# MainBoard.net
KiCad netlist of a schematic drawn in Altium Designer
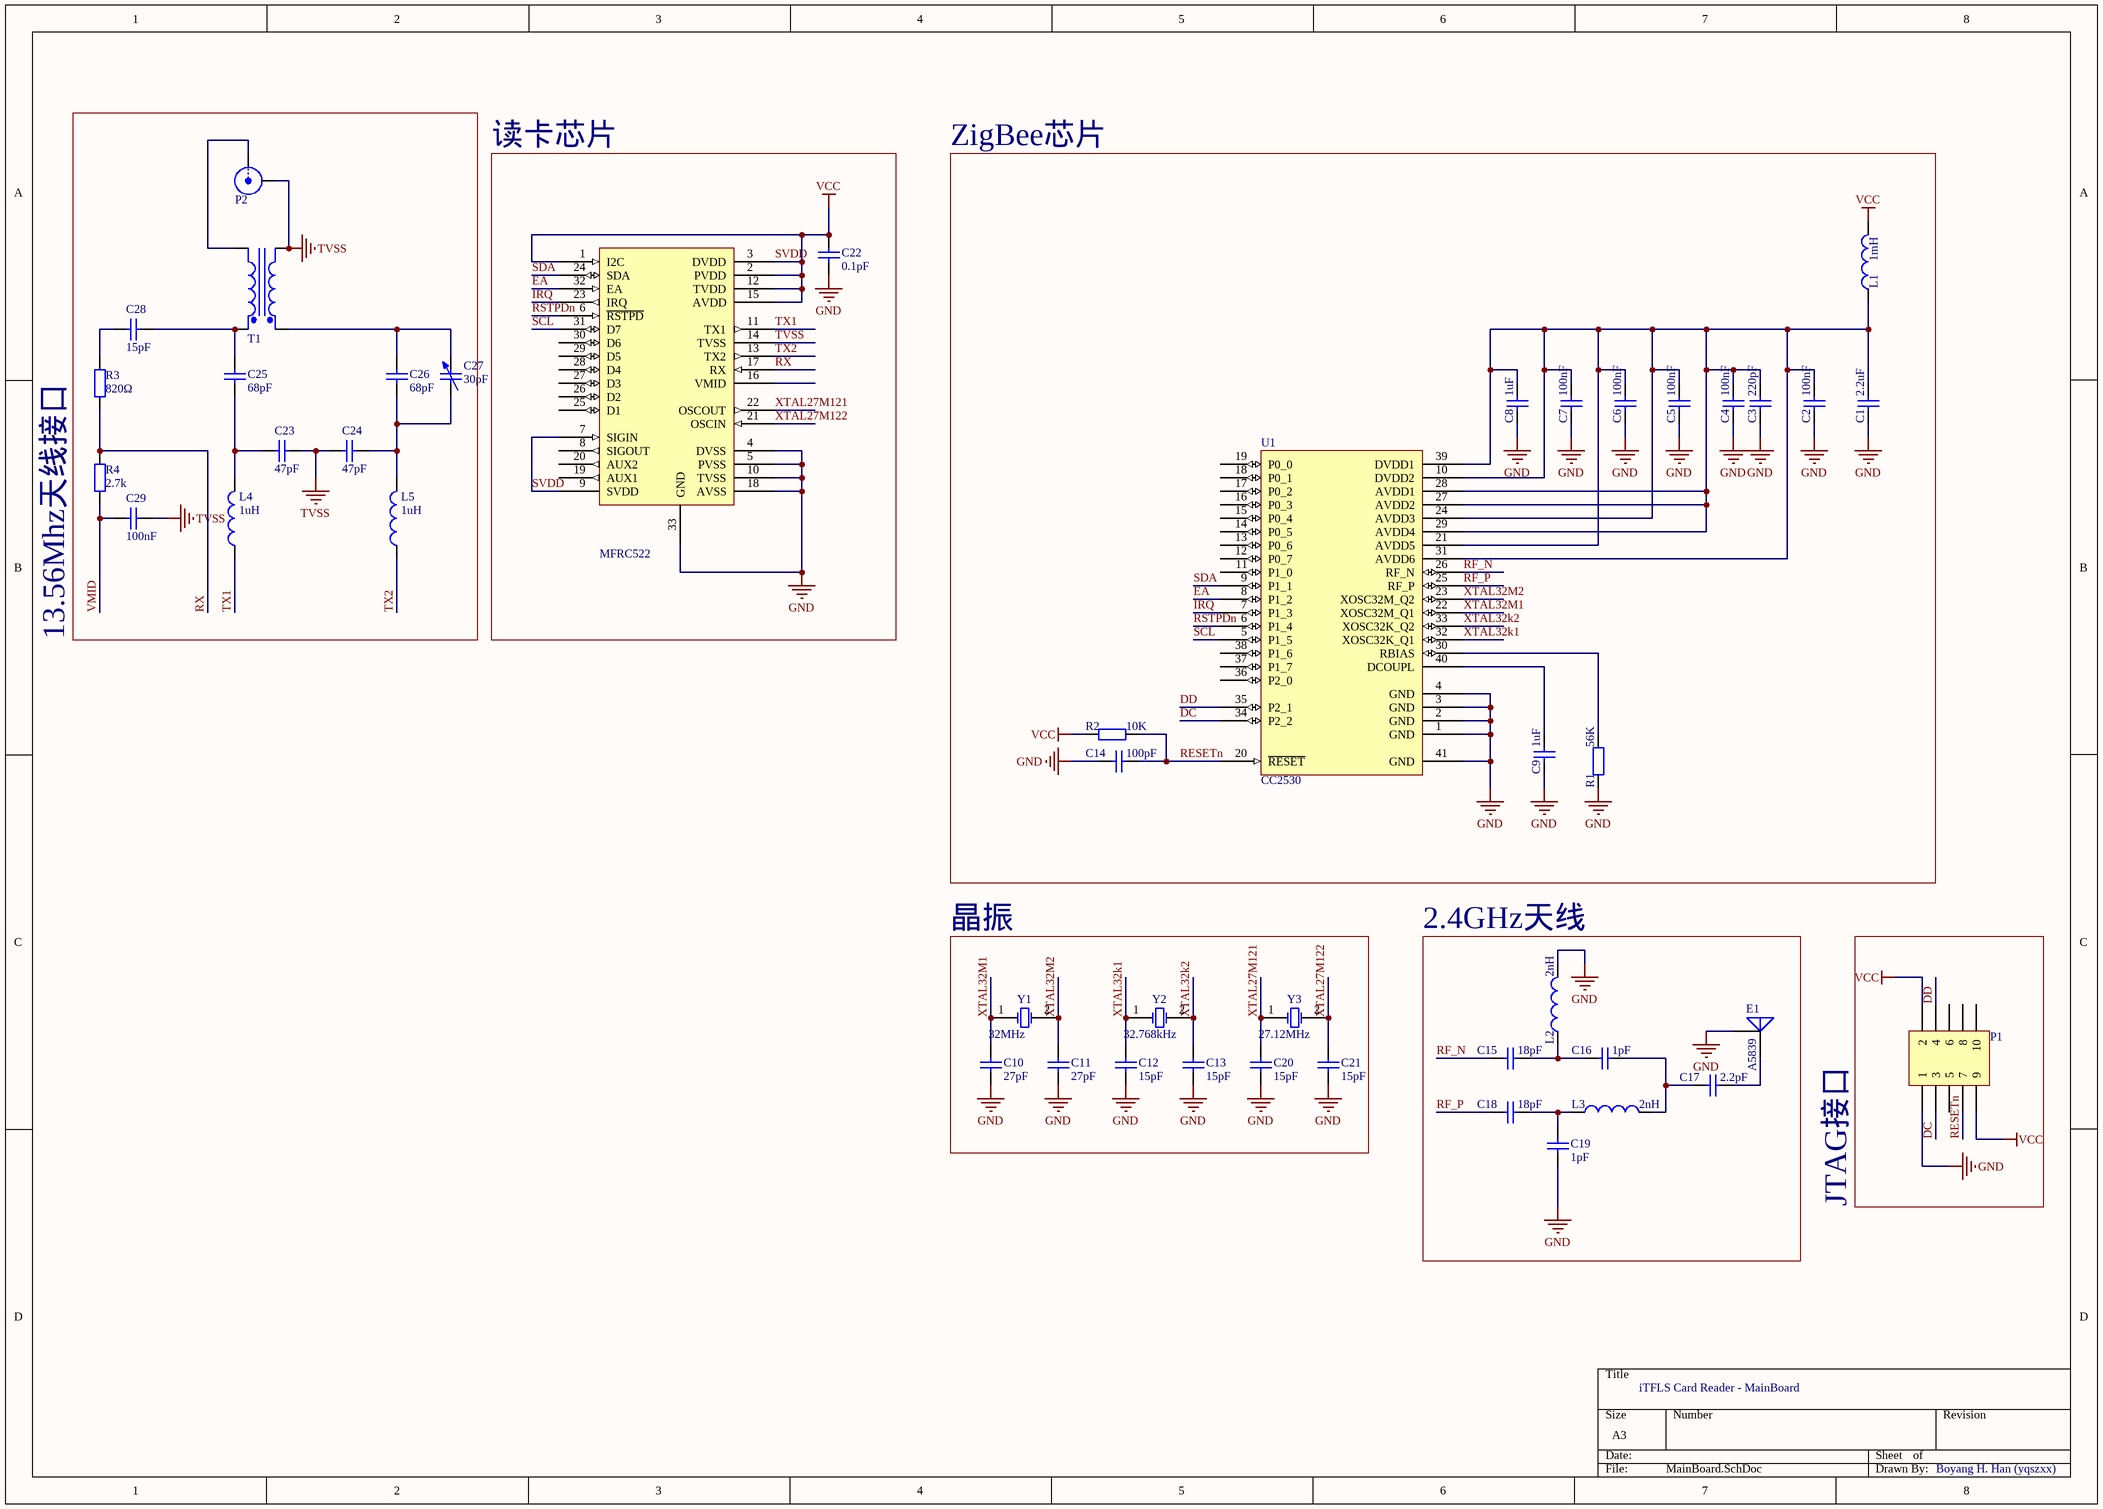
[diagram p0: MainBoard.SchDoc]

(export (version "E")
  (design (tool "Eeschema 10.0.6"))
  (components
    (comp (ref "C1")
      (value "2.2uF")
      (footprint "0603")
      (description "Capacitor")
      (fields (field (name "Comment") "Cap") (field (name "PUBLISHER") "Altium Limited"))
      (libsource (lib "Miscellaneous Devices") (part "Cap"))
    )
    (comp (ref "C2")
      (value "100nF")
      (footprint "0603")
      (description "Capacitor")
      (fields (field (name "Comment") "Cap") (field (name "PUBLISHER") "Altium Limited"))
      (libsource (lib "Miscellaneous Devices") (part "Cap"))
    )
    (comp (ref "C3")
      (value "220pF")
      (footprint "0603")
      (description "Capacitor")
      (fields (field (name "Comment") "Cap") (field (name "PUBLISHER") "Altium Limited"))
      (libsource (lib "Miscellaneous Devices") (part "Cap"))
    )
    (comp (ref "C4")
      (value "100nF")
      (footprint "0603")
      (description "Capacitor")
      (fields (field (name "Comment") "Cap") (field (name "PUBLISHER") "Altium Limited"))
      (libsource (lib "Miscellaneous Devices") (part "Cap"))
    )
    (comp (ref "C5")
      (value "100nF")
      (footprint "0603")
      (description "Capacitor")
      (fields (field (name "Comment") "Cap") (field (name "PUBLISHER") "Altium Limited"))
      (libsource (lib "Miscellaneous Devices") (part "Cap"))
    )
    (comp (ref "C6")
      (value "100nF")
      (footprint "0603")
      (description "Capacitor")
      (fields (field (name "Comment") "Cap") (field (name "PUBLISHER") "Altium Limited"))
      (libsource (lib "Miscellaneous Devices") (part "Cap"))
    )
    (comp (ref "C7")
      (value "100nF")
      (footprint "0603")
      (description "Capacitor")
      (fields (field (name "Comment") "Cap") (field (name "PUBLISHER") "Altium Limited"))
      (libsource (lib "Miscellaneous Devices") (part "Cap"))
    )
    (comp (ref "C8")
      (value "1uF")
      (footprint "0603")
      (description "Capacitor")
      (fields (field (name "Comment") "Cap") (field (name "PUBLISHER") "Altium Limited"))
      (libsource (lib "Miscellaneous Devices") (part "Cap"))
    )
    (comp (ref "C9")
      (value "1uF")
      (footprint "0603")
      (description "Capacitor")
      (fields (field (name "Comment") "Cap") (field (name "PUBLISHER") "Altium Limited"))
      (libsource (lib "Miscellaneous Devices") (part "Cap"))
    )
    (comp (ref "C10")
      (value "27pF")
      (footprint "0603")
      (description "Capacitor")
      (fields (field (name "Comment") "Cap") (field (name "PUBLISHER") "Altium Limited"))
      (libsource (lib "Miscellaneous Devices") (part "Cap"))
    )
    (comp (ref "C11")
      (value "27pF")
      (footprint "0603")
      (description "Capacitor")
      (fields (field (name "Comment") "Cap") (field (name "PUBLISHER") "Altium Limited"))
      (libsource (lib "Miscellaneous Devices") (part "Cap"))
    )
    (comp (ref "C12")
      (value "15pF")
      (footprint "0603")
      (description "Capacitor")
      (fields (field (name "Comment") "Cap") (field (name "PUBLISHER") "Altium Limited"))
      (libsource (lib "Miscellaneous Devices") (part "Cap"))
    )
    (comp (ref "C13")
      (value "15pF")
      (footprint "0603")
      (description "Capacitor")
      (fields (field (name "Comment") "Cap") (field (name "PUBLISHER") "Altium Limited"))
      (libsource (lib "Miscellaneous Devices") (part "Cap"))
    )
    (comp (ref "C14")
      (value "100pF")
      (footprint "0603")
      (description "Capacitor")
      (fields (field (name "Comment") "Cap") (field (name "PUBLISHER") "Altium Limited"))
      (libsource (lib "Miscellaneous Devices") (part "Cap"))
    )
    (comp (ref "C15")
      (value "18pF")
      (footprint "0603")
      (description "Capacitor")
      (fields (field (name "Comment") "Cap") (field (name "PUBLISHER") "Altium Limited"))
      (libsource (lib "Miscellaneous Devices") (part "Cap"))
    )
    (comp (ref "C16")
      (value "1pF")
      (footprint "0603")
      (description "Capacitor")
      (fields (field (name "Comment") "Cap") (field (name "PUBLISHER") "Altium Limited"))
      (libsource (lib "Miscellaneous Devices") (part "Cap"))
    )
    (comp (ref "C17")
      (value "2.2pF")
      (footprint "0603")
      (description "Capacitor")
      (fields (field (name "Comment") "Cap") (field (name "PUBLISHER") "Altium Limited"))
      (libsource (lib "Miscellaneous Devices") (part "Cap"))
    )
    (comp (ref "C18")
      (value "18pF")
      (footprint "0603")
      (description "Capacitor")
      (fields (field (name "Comment") "Cap") (field (name "PUBLISHER") "Altium Limited"))
      (libsource (lib "Miscellaneous Devices") (part "Cap"))
    )
    (comp (ref "C19")
      (value "1pF")
      (footprint "0603")
      (description "Capacitor")
      (fields (field (name "Comment") "Cap") (field (name "PUBLISHER") "Altium Limited"))
      (libsource (lib "Miscellaneous Devices") (part "Cap"))
    )
    (comp (ref "C20")
      (value "15pF")
      (footprint "0603")
      (description "Capacitor")
      (fields (field (name "Comment") "Cap") (field (name "PUBLISHER") "Altium Limited"))
      (libsource (lib "Miscellaneous Devices") (part "Cap"))
    )
    (comp (ref "C21")
      (value "15pF")
      (footprint "0603")
      (description "Capacitor")
      (fields (field (name "Comment") "Cap") (field (name "PUBLISHER") "Altium Limited"))
      (libsource (lib "Miscellaneous Devices") (part "Cap"))
    )
    (comp (ref "C22")
      (value "0.1pF")
      (footprint "0603")
      (description "Capacitor")
      (fields (field (name "Comment") "Cap") (field (name "PUBLISHER") "Altium Limited"))
      (libsource (lib "Miscellaneous Devices") (part "Cap"))
    )
    (comp (ref "C23")
      (value "47pF")
      (footprint "0603")
      (description "Capacitor")
      (fields (field (name "Comment") "Cap") (field (name "PUBLISHER") "Altium Limited"))
      (libsource (lib "Miscellaneous Devices") (part "Cap"))
    )
    (comp (ref "C24")
      (value "47pF")
      (footprint "0603")
      (description "Capacitor")
      (fields (field (name "Comment") "Cap") (field (name "PUBLISHER") "Altium Limited"))
      (libsource (lib "Miscellaneous Devices") (part "Cap"))
    )
    (comp (ref "C25")
      (value "68pF")
      (footprint "0603")
      (description "Capacitor")
      (fields (field (name "Comment") "Cap") (field (name "PUBLISHER") "Altium Limited"))
      (libsource (lib "Miscellaneous Devices") (part "Cap"))
    )
    (comp (ref "C26")
      (value "68pF")
      (footprint "0603")
      (description "Capacitor")
      (fields (field (name "Comment") "Cap") (field (name "PUBLISHER") "Altium Limited"))
      (libsource (lib "Miscellaneous Devices") (part "Cap"))
    )
    (comp (ref "C27")
      (value "30pF")
      (footprint "4x4VC")
      (description "Variable or Adjustable Capacitor")
      (fields (field (name "Comment") "Cap Var") (field (name "PUBLISHER") "Altium Limited"))
      (libsource (lib "Miscellaneous Devices") (part "Cap Var"))
    )
    (comp (ref "C28")
      (value "15pF")
      (footprint "0603")
      (description "Capacitor")
      (fields (field (name "Comment") "Cap") (field (name "PUBLISHER") "Altium Limited"))
      (libsource (lib "Miscellaneous Devices") (part "Cap"))
    )
    (comp (ref "C29")
      (value "100nF")
      (footprint "0603")
      (description "Capacitor")
      (fields (field (name "Comment") "Cap") (field (name "PUBLISHER") "Altium Limited"))
      (libsource (lib "Miscellaneous Devices") (part "Cap"))
    )
    (comp (ref "E1") (value "A5839") (footprint "A5839") (libsource (lib "A5839") (part "A5839")))
    (comp (ref "L1")
      (value "1mH")
      (footprint "0603")
      (description "Inductor")
      (fields (field (name "PUBLISHER") "Altium Limited"))
      (libsource (lib "Miscellaneous Devices") (part "Inductor"))
    )
    (comp (ref "L2")
      (value "2nH")
      (footprint "0603")
      (description "Inductor")
      (fields (field (name "PUBLISHER") "Altium Limited"))
      (libsource (lib "Miscellaneous Devices") (part "Inductor"))
    )
    (comp (ref "L3")
      (value "2nH")
      (footprint "0603")
      (description "Inductor")
      (fields (field (name "PUBLISHER") "Altium Limited"))
      (libsource (lib "Miscellaneous Devices") (part "Inductor"))
    )
    (comp (ref "L4")
      (value "1uH")
      (footprint "0603")
      (description "Inductor")
      (fields (field (name "PUBLISHER") "Altium Limited"))
      (libsource (lib "Miscellaneous Devices") (part "Inductor"))
    )
    (comp (ref "L5")
      (value "1uH")
      (footprint "0603")
      (description "Inductor")
      (fields (field (name "PUBLISHER") "Altium Limited"))
      (libsource (lib "Miscellaneous Devices") (part "Inductor"))
    )
    (comp (ref "P1")
      (value "Header 5X2")
      (footprint "HDR2X5")
      (description "Header, 5-Pin, Dual row")
      (fields (field (name "PUBLISHER") "Altium Limited"))
      (libsource (lib "Miscellaneous Connectors") (part "Header 5X2"))
    )
    (comp (ref "P2")
      (value "U.FL")
      (footprint "U.FL")
      (description "SMB Straight Connector")
      (fields (field (name "PUBLISHER") "Altium Limited"))
      (libsource (lib "Miscellaneous Connectors") (part "SMB"))
    )
    (comp (ref "R1")
      (value "56K")
      (footprint "0603")
      (description "Resistor")
      (fields (field (name "Comment") "Res2") (field (name "PUBLISHER") "Altium Limited"))
      (libsource (lib "") (part "Res2_1"))
    )
    (comp (ref "R2")
      (value "10K")
      (footprint "0603")
      (description "Resistor")
      (fields (field (name "Comment") "Res2") (field (name "PUBLISHER") "Altium Limited"))
      (libsource (lib "Miscellaneous Devices") (part "Res2"))
    )
    (comp (ref "R3")
      (value "820Ω")
      (footprint "0603")
      (description "Resistor")
      (fields (field (name "Comment") "Res2") (field (name "PUBLISHER") "Altium Limited"))
      (libsource (lib "") (part "Res2_1"))
    )
    (comp (ref "R4")
      (value "2.7k")
      (footprint "0603")
      (description "Resistor")
      (fields (field (name "Comment") "Res2") (field (name "PUBLISHER") "Altium Limited"))
      (libsource (lib "") (part "Res2_1"))
    )
    (comp (ref "T1")
      (value "1812WBT-3")
      (footprint "1812WBT-3")
      (libsource (lib "Coilcraft 1812WBT-3") (part "1812WBT-3"))
    )
    (comp (ref "U1") (value "CC2530") (footprint "QFN40") (libsource (lib "CC2530") (part "CC2530")))
    (comp (ref "U2") (value "MFRC522") (footprint "QFN32") (libsource (lib "MFRC522") (part "MFRC522")))
    (comp (ref "Y1")
      (value "32MHz")
      (footprint "XTAL3225")
      (description "Crystal Oscillator")
      (fields (field (name "Comment") "XTAL") (field (name "PUBLISHER") "Altium Limited"))
      (libsource (lib "Miscellaneous Devices") (part "XTAL"))
    )
    (comp (ref "Y2")
      (value "32.768kHz")
      (footprint "XTAL3215")
      (description "Crystal Oscillator")
      (fields (field (name "Comment") "XTAL") (field (name "PUBLISHER") "Altium Limited"))
      (libsource (lib "Miscellaneous Devices") (part "XTAL"))
    )
    (comp (ref "Y3")
      (value "27.12MHz")
      (footprint "XTAL3225")
      (description "Crystal Oscillator")
      (fields (field (name "Comment") "XTAL") (field (name "PUBLISHER") "Altium Limited"))
      (libsource (lib "Miscellaneous Devices") (part "XTAL"))
    )
  )
  (nets
    (net (code "1") (name "/DC") (class "Default")
      (node (ref "P1") (pin "3") (pinfunction "3_3") (pintype "passive"))
      (node (ref "U1") (pin "34") (pinfunction "P2_2_34") (pintype "bidirectional"))
    )
    (net (code "2") (name "/DD") (class "Default")
      (node (ref "P1") (pin "4") (pinfunction "4_4") (pintype "passive"))
      (node (ref "U1") (pin "35") (pinfunction "P2_1_35") (pintype "bidirectional"))
    )
    (net (code "3") (name "/EA") (class "Default")
      (node (ref "U1") (pin "8") (pinfunction "P1_2_8") (pintype "bidirectional"))
      (node (ref "U2") (pin "32") (pinfunction "EA_32") (pintype "input"))
    )
    (net (code "4") (name "/IRQ") (class "Default")
      (node (ref "U1") (pin "7") (pinfunction "P1_3_7") (pintype "bidirectional"))
      (node (ref "U2") (pin "23") (pinfunction "IRQ_23") (pintype "output"))
    )
    (net (code "5") (name "/RESETn") (class "Default")
      (node (ref "C14") (pin "2") (pinfunction "2_2") (pintype "passive"))
      (node (ref "P1") (pin "7") (pinfunction "7_7") (pintype "passive"))
      (node (ref "R2") (pin "2") (pinfunction "2_2") (pintype "passive"))
      (node (ref "U1") (pin "20") (pinfunction "~{RESET}_20") (pintype "input"))
    )
    (net (code "6") (name "/RF_N") (class "Default")
      (node (ref "C15") (pin "1") (pinfunction "1_1") (pintype "passive"))
      (node (ref "U1") (pin "26") (pinfunction "RF_N_26") (pintype "bidirectional"))
    )
    (net (code "7") (name "/RF_P") (class "Default")
      (node (ref "C18") (pin "1") (pinfunction "1_1") (pintype "passive"))
      (node (ref "U1") (pin "25") (pinfunction "RF_P_25") (pintype "bidirectional"))
    )
    (net (code "8") (name "/RSTPDn") (class "Default")
      (node (ref "U1") (pin "6") (pinfunction "P1_4_6") (pintype "bidirectional"))
      (node (ref "U2") (pin "6") (pinfunction "~{RSTPD}_6") (pintype "input"))
    )
    (net (code "9") (name "/RX") (class "Default")
      (node (ref "R3") (pin "1") (pinfunction "1_1") (pintype "passive"))
      (node (ref "R4") (pin "2") (pinfunction "2_2") (pintype "passive"))
      (node (ref "U2") (pin "17") (pinfunction "RX_17") (pintype "input"))
    )
    (net (code "10") (name "/SCL") (class "Default")
      (node (ref "U1") (pin "5") (pinfunction "P1_5_5") (pintype "bidirectional"))
      (node (ref "U2") (pin "31") (pinfunction "D7_31") (pintype "bidirectional"))
    )
    (net (code "11") (name "/SDA") (class "Default")
      (node (ref "U1") (pin "9") (pinfunction "P1_1_9") (pintype "bidirectional"))
      (node (ref "U2") (pin "24") (pinfunction "SDA_24") (pintype "bidirectional"))
    )
    (net (code "12") (name "/TX1") (class "Default")
      (node (ref "L4") (pin "1") (pinfunction "1_1") (pintype "passive"))
      (node (ref "U2") (pin "11") (pinfunction "TX1_11") (pintype "output"))
    )
    (net (code "13") (name "/TX2") (class "Default")
      (node (ref "L5") (pin "1") (pinfunction "1_1") (pintype "passive"))
      (node (ref "U2") (pin "13") (pinfunction "TX2_13") (pintype "output"))
    )
    (net (code "14") (name "/VMID") (class "Default")
      (node (ref "C29") (pin "2") (pinfunction "2_2") (pintype "passive"))
      (node (ref "R4") (pin "1") (pinfunction "1_1") (pintype "passive"))
    )
    (net (code "15") (name "/XTAL27M121") (class "Default")
      (node (ref "C20") (pin "2") (pinfunction "2_2") (pintype "passive"))
      (node (ref "U2") (pin "22") (pinfunction "OSCOUT_22") (pintype "output"))
      (node (ref "Y3") (pin "1") (pinfunction "OSC1_1") (pintype "passive"))
    )
    (net (code "16") (name "/XTAL27M122") (class "Default")
      (node (ref "C21") (pin "2") (pinfunction "2_2") (pintype "passive"))
      (node (ref "U2") (pin "21") (pinfunction "OSCIN_21") (pintype "input"))
      (node (ref "Y3") (pin "2") (pinfunction "OSC2_2") (pintype "passive"))
    )
    (net (code "17") (name "/XTAL32M1") (class "Default")
      (node (ref "C10") (pin "2") (pinfunction "2_2") (pintype "passive"))
      (node (ref "U1") (pin "22") (pinfunction "XOSC32M_Q1_22") (pintype "bidirectional"))
      (node (ref "Y1") (pin "1") (pinfunction "OSC1_1") (pintype "passive"))
    )
    (net (code "18") (name "/XTAL32M2") (class "Default")
      (node (ref "C11") (pin "2") (pinfunction "2_2") (pintype "passive"))
      (node (ref "U1") (pin "23") (pinfunction "XOSC32M_Q2_23") (pintype "bidirectional"))
      (node (ref "Y1") (pin "2") (pinfunction "OSC2_2") (pintype "passive"))
    )
    (net (code "19") (name "/XTAL32k1") (class "Default")
      (node (ref "C12") (pin "2") (pinfunction "2_2") (pintype "passive"))
      (node (ref "U1") (pin "32") (pinfunction "XOSC32K_Q1_32") (pintype "bidirectional"))
      (node (ref "Y2") (pin "1") (pinfunction "OSC1_1") (pintype "passive"))
    )
    (net (code "20") (name "/XTAL32k2") (class "Default")
      (node (ref "C13") (pin "2") (pinfunction "2_2") (pintype "passive"))
      (node (ref "U1") (pin "33") (pinfunction "XOSC32K_Q2_33") (pintype "bidirectional"))
      (node (ref "Y2") (pin "2") (pinfunction "OSC2_2") (pintype "passive"))
    )
    (net (code "21") (name "GND") (class "Default")
      (node (ref "C1") (pin "1") (pinfunction "1_1") (pintype "passive"))
      (node (ref "C10") (pin "1") (pinfunction "1_1") (pintype "passive"))
      (node (ref "C11") (pin "1") (pinfunction "1_1") (pintype "passive"))
      (node (ref "C12") (pin "1") (pinfunction "1_1") (pintype "passive"))
      (node (ref "C13") (pin "1") (pinfunction "1_1") (pintype "passive"))
      (node (ref "C14") (pin "1") (pinfunction "1_1") (pintype "passive"))
      (node (ref "C19") (pin "1") (pinfunction "1_1") (pintype "passive"))
      (node (ref "C2") (pin "1") (pinfunction "1_1") (pintype "passive"))
      (node (ref "C20") (pin "1") (pinfunction "1_1") (pintype "passive"))
      (node (ref "C21") (pin "1") (pinfunction "1_1") (pintype "passive"))
      (node (ref "C22") (pin "1") (pinfunction "1_1") (pintype "passive"))
      (node (ref "C3") (pin "1") (pinfunction "1_1") (pintype "passive"))
      (node (ref "C4") (pin "1") (pinfunction "1_1") (pintype "passive"))
      (node (ref "C5") (pin "1") (pinfunction "1_1") (pintype "passive"))
      (node (ref "C6") (pin "1") (pinfunction "1_1") (pintype "passive"))
      (node (ref "C7") (pin "1") (pinfunction "1_1") (pintype "passive"))
      (node (ref "C8") (pin "1") (pinfunction "1_1") (pintype "passive"))
      (node (ref "C9") (pin "1") (pinfunction "1_1") (pintype "passive"))
      (node (ref "E1") (pin "2") (pinfunction "GND_2") (pintype "passive"))
      (node (ref "L2") (pin "2") (pinfunction "2_2") (pintype "passive"))
      (node (ref "P1") (pin "1") (pinfunction "1_1") (pintype "passive"))
      (node (ref "R1") (pin "1") (pinfunction "1_1") (pintype "passive"))
      (node (ref "U1") (pin "1") (pinfunction "GND_1") (pintype "power_in"))
      (node (ref "U1") (pin "2") (pinfunction "GND_2") (pintype "power_in"))
      (node (ref "U1") (pin "3") (pinfunction "GND_3") (pintype "power_in"))
      (node (ref "U1") (pin "4") (pinfunction "GND_4") (pintype "power_in"))
      (node (ref "U1") (pin "41") (pinfunction "GND_41") (pintype "power_in"))
      (node (ref "U2") (pin "10") (pinfunction "TVSS_10") (pintype "power_in"))
      (node (ref "U2") (pin "18") (pinfunction "AVSS_18") (pintype "power_in"))
      (node (ref "U2") (pin "33") (pinfunction "GND_33") (pintype "power_in"))
      (node (ref "U2") (pin "4") (pinfunction "DVSS_4") (pintype "power_in"))
      (node (ref "U2") (pin "5") (pinfunction "PVSS_5") (pintype "power_in"))
    )
    (net (code "22") (name "Net-(C15-Pad2)") (class "Default")
      (node (ref "C15") (pin "2") (pinfunction "2_2") (pintype "passive"))
      (node (ref "C16") (pin "1") (pinfunction "1_1") (pintype "passive"))
      (node (ref "L2") (pin "1") (pinfunction "1_1") (pintype "passive"))
    )
    (net (code "23") (name "Net-(C16-Pad2)") (class "Default")
      (node (ref "C16") (pin "2") (pinfunction "2_2") (pintype "passive"))
      (node (ref "C17") (pin "1") (pinfunction "1_1") (pintype "passive"))
      (node (ref "L3") (pin "2") (pinfunction "2_2") (pintype "passive"))
    )
    (net (code "24") (name "Net-(C18-Pad2)") (class "Default")
      (node (ref "C18") (pin "2") (pinfunction "2_2") (pintype "passive"))
      (node (ref "C19") (pin "2") (pinfunction "2_2") (pintype "passive"))
      (node (ref "L3") (pin "1") (pinfunction "1_1") (pintype "passive"))
    )
    (net (code "25") (name "Net-(C23-Pad2)") (class "Default")
      (node (ref "C23") (pin "2") (pinfunction "2_2") (pintype "passive"))
      (node (ref "C25") (pin "1") (pinfunction "1_1") (pintype "passive"))
      (node (ref "L4") (pin "2") (pinfunction "2_2") (pintype "passive"))
    )
    (net (code "26") (name "Net-(C24-Pad1)") (class "Default")
      (node (ref "C24") (pin "1") (pinfunction "1_1") (pintype "passive"))
      (node (ref "C26") (pin "1") (pinfunction "1_1") (pintype "passive"))
      (node (ref "C27") (pin "1") (pinfunction "1_1") (pintype "passive"))
      (node (ref "L5") (pin "2") (pinfunction "2_2") (pintype "passive"))
    )
    (net (code "27") (name "Net-(C28-Pad2)") (class "Default")
      (node (ref "C28") (pin "2") (pinfunction "2_2") (pintype "passive"))
      (node (ref "R3") (pin "2") (pinfunction "2_2") (pintype "passive"))
    )
    (net (code "28") (name "Net-(E1-FEED)") (class "Default")
      (node (ref "C17") (pin "2") (pinfunction "2_2") (pintype "passive"))
      (node (ref "E1") (pin "1") (pinfunction "FEED_1") (pintype "passive"))
    )
    (net (code "29") (name "Net-(P2-X)") (class "Default")
      (node (ref "P2") (pin "1") (pinfunction "X_1") (pintype "passive"))
      (node (ref "T1") (pin "3") (pinfunction "Sec-_3") (pintype "passive"))
    )
    (net (code "30") (name "Net-(T1-Pri+)") (class "Default")
      (node (ref "C26") (pin "2") (pinfunction "2_2") (pintype "passive"))
      (node (ref "C27") (pin "2") (pinfunction "2_2") (pintype "passive"))
      (node (ref "T1") (pin "1") (pinfunction "Pri+_1") (pintype "passive"))
    )
    (net (code "31") (name "Net-(T1-Sec+)") (class "Default")
      (node (ref "C25") (pin "2") (pinfunction "2_2") (pintype "passive"))
      (node (ref "C28") (pin "1") (pinfunction "1_1") (pintype "passive"))
      (node (ref "T1") (pin "4") (pinfunction "Sec+_4") (pintype "passive"))
    )
    (net (code "32") (name "Net-(U1-AVDD1)") (class "Default")
      (node (ref "C1") (pin "2") (pinfunction "2_2") (pintype "passive"))
      (node (ref "C2") (pin "2") (pinfunction "2_2") (pintype "passive"))
      (node (ref "C3") (pin "2") (pinfunction "2_2") (pintype "passive"))
      (node (ref "C4") (pin "2") (pinfunction "2_2") (pintype "passive"))
      (node (ref "C5") (pin "2") (pinfunction "2_2") (pintype "passive"))
      (node (ref "C6") (pin "2") (pinfunction "2_2") (pintype "passive"))
      (node (ref "C7") (pin "2") (pinfunction "2_2") (pintype "passive"))
      (node (ref "C8") (pin "2") (pinfunction "2_2") (pintype "passive"))
      (node (ref "L1") (pin "1") (pinfunction "1_1") (pintype "passive"))
      (node (ref "U1") (pin "10") (pinfunction "DVDD2_10") (pintype "power_in"))
      (node (ref "U1") (pin "21") (pinfunction "AVDD5_21") (pintype "power_in"))
      (node (ref "U1") (pin "24") (pinfunction "AVDD3_24") (pintype "power_in"))
      (node (ref "U1") (pin "27") (pinfunction "AVDD2_27") (pintype "power_in"))
      (node (ref "U1") (pin "28") (pinfunction "AVDD1_28") (pintype "power_in"))
      (node (ref "U1") (pin "29") (pinfunction "AVDD4_29") (pintype "power_in"))
      (node (ref "U1") (pin "31") (pinfunction "AVDD6_31") (pintype "power_in"))
      (node (ref "U1") (pin "39") (pinfunction "DVDD1_39") (pintype "power_in"))
    )
    (net (code "33") (name "Net-(U1-DCOUPL)") (class "Default")
      (node (ref "C9") (pin "2") (pinfunction "2_2") (pintype "passive"))
      (node (ref "U1") (pin "40") (pinfunction "DCOUPL_40") (pintype "power_in"))
    )
    (net (code "34") (name "Net-(U1-RBIAS)") (class "Default")
      (node (ref "R1") (pin "2") (pinfunction "2_2") (pintype "passive"))
      (node (ref "U1") (pin "30") (pinfunction "RBIAS_30") (pintype "bidirectional"))
    )
    (net (code "35") (name "TVSS") (class "Default")
      (node (ref "C23") (pin "1") (pinfunction "1_1") (pintype "passive"))
      (node (ref "C24") (pin "2") (pinfunction "2_2") (pintype "passive"))
      (node (ref "C29") (pin "1") (pinfunction "1_1") (pintype "passive"))
      (node (ref "P2") (pin "2") (pinfunction "Y_2") (pintype "passive"))
      (node (ref "T1") (pin "2") (pinfunction "Pri-_2") (pintype "passive"))
      (node (ref "U2") (pin "14") (pinfunction "TVSS_14") (pintype "power_in"))
    )
    (net (code "36") (name "VCC") (class "Default")
      (node (ref "C22") (pin "2") (pinfunction "2_2") (pintype "passive"))
      (node (ref "L1") (pin "2") (pinfunction "2_2") (pintype "passive"))
      (node (ref "P1") (pin "2") (pinfunction "2_2") (pintype "passive"))
      (node (ref "P1") (pin "9") (pinfunction "9_9") (pintype "passive"))
      (node (ref "R2") (pin "1") (pinfunction "1_1") (pintype "passive"))
      (node (ref "U2") (pin "1") (pinfunction "I2C_1") (pintype "input"))
      (node (ref "U2") (pin "12") (pinfunction "TVDD_12") (pintype "power_in"))
      (node (ref "U2") (pin "15") (pinfunction "AVDD_15") (pintype "power_in"))
      (node (ref "U2") (pin "2") (pinfunction "PVDD_2") (pintype "power_in"))
      (node (ref "U2") (pin "3") (pinfunction "DVDD_3") (pintype "power_in"))
      (node (ref "U2") (pin "7") (pinfunction "SIGIN_7") (pintype "input"))
      (node (ref "U2") (pin "9") (pinfunction "SVDD_9") (pintype "power_in"))
    )
    (net (code "37") (name "unconnected-(P1-Pad5)") (class "Default")
      (node (ref "P1") (pin "5") (pinfunction "5_5") (pintype "passive"))
    )
    (net (code "38") (name "unconnected-(P1-Pad6)") (class "Default")
      (node (ref "P1") (pin "6") (pinfunction "6_6") (pintype "passive"))
    )
    (net (code "39") (name "unconnected-(P1-Pad8)") (class "Default")
      (node (ref "P1") (pin "8") (pinfunction "8_8") (pintype "passive"))
    )
    (net (code "40") (name "unconnected-(P1-Pad10)") (class "Default")
      (node (ref "P1") (pin "10") (pinfunction "10_10") (pintype "passive"))
    )
    (net (code "41") (name "unconnected-(U1-P0_0-Pad19)") (class "Default")
      (node (ref "U1") (pin "19") (pinfunction "P0_0_19") (pintype "bidirectional"))
    )
    (net (code "42") (name "unconnected-(U1-P0_1-Pad18)") (class "Default")
      (node (ref "U1") (pin "18") (pinfunction "P0_1_18") (pintype "bidirectional"))
    )
    (net (code "43") (name "unconnected-(U1-P0_2-Pad17)") (class "Default")
      (node (ref "U1") (pin "17") (pinfunction "P0_2_17") (pintype "bidirectional"))
    )
    (net (code "44") (name "unconnected-(U1-P0_3-Pad16)") (class "Default")
      (node (ref "U1") (pin "16") (pinfunction "P0_3_16") (pintype "bidirectional"))
    )
    (net (code "45") (name "unconnected-(U1-P0_4-Pad15)") (class "Default")
      (node (ref "U1") (pin "15") (pinfunction "P0_4_15") (pintype "bidirectional"))
    )
    (net (code "46") (name "unconnected-(U1-P0_5-Pad14)") (class "Default")
      (node (ref "U1") (pin "14") (pinfunction "P0_5_14") (pintype "bidirectional"))
    )
    (net (code "47") (name "unconnected-(U1-P0_6-Pad13)") (class "Default")
      (node (ref "U1") (pin "13") (pinfunction "P0_6_13") (pintype "bidirectional"))
    )
    (net (code "48") (name "unconnected-(U1-P0_7-Pad12)") (class "Default")
      (node (ref "U1") (pin "12") (pinfunction "P0_7_12") (pintype "bidirectional"))
    )
    (net (code "49") (name "unconnected-(U1-P1_0-Pad11)") (class "Default")
      (node (ref "U1") (pin "11") (pinfunction "P1_0_11") (pintype "bidirectional"))
    )
    (net (code "50") (name "unconnected-(U1-P1_6-Pad38)") (class "Default")
      (node (ref "U1") (pin "38") (pinfunction "P1_6_38") (pintype "bidirectional"))
    )
    (net (code "51") (name "unconnected-(U1-P1_7-Pad37)") (class "Default")
      (node (ref "U1") (pin "37") (pinfunction "P1_7_37") (pintype "bidirectional"))
    )
    (net (code "52") (name "unconnected-(U1-P2_0-Pad36)") (class "Default")
      (node (ref "U1") (pin "36") (pinfunction "P2_0_36") (pintype "bidirectional"))
    )
    (net (code "53") (name "unconnected-(U2-AUX1-Pad19)") (class "Default")
      (node (ref "U2") (pin "19") (pinfunction "AUX1_19") (pintype "output"))
    )
    (net (code "54") (name "unconnected-(U2-AUX2-Pad20)") (class "Default")
      (node (ref "U2") (pin "20") (pinfunction "AUX2_20") (pintype "output"))
    )
    (net (code "55") (name "unconnected-(U2-D1-Pad25)") (class "Default")
      (node (ref "U2") (pin "25") (pinfunction "D1_25") (pintype "bidirectional"))
    )
    (net (code "56") (name "unconnected-(U2-D2-Pad26)") (class "Default")
      (node (ref "U2") (pin "26") (pinfunction "D2_26") (pintype "bidirectional"))
    )
    (net (code "57") (name "unconnected-(U2-D3-Pad27)") (class "Default")
      (node (ref "U2") (pin "27") (pinfunction "D3_27") (pintype "bidirectional"))
    )
    (net (code "58") (name "unconnected-(U2-D4-Pad28)") (class "Default")
      (node (ref "U2") (pin "28") (pinfunction "D4_28") (pintype "bidirectional"))
    )
    (net (code "59") (name "unconnected-(U2-D5-Pad29)") (class "Default")
      (node (ref "U2") (pin "29") (pinfunction "D5_29") (pintype "bidirectional"))
    )
    (net (code "60") (name "unconnected-(U2-D6-Pad30)") (class "Default")
      (node (ref "U2") (pin "30") (pinfunction "D6_30") (pintype "bidirectional"))
    )
    (net (code "61") (name "unconnected-(U2-SIGOUT-Pad8)") (class "Default")
      (node (ref "U2") (pin "8") (pinfunction "SIGOUT_8") (pintype "output"))
    )
    (net (code "62") (name "unconnected-(U2-VMID-Pad16)") (class "Default")
      (node (ref "U2") (pin "16") (pinfunction "VMID_16") (pintype "power_in"))
    )
  )
)
